# 03_MCU.net
KiCad netlist of a schematic drawn in Altium Designer
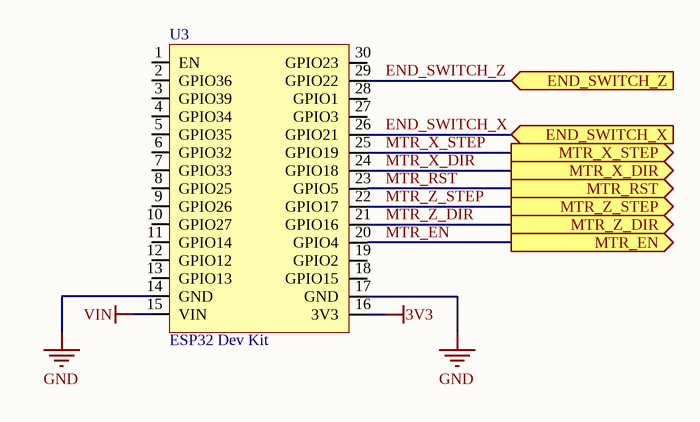
[diagram p0: 03_MCU.SchDoc]

(export (version "E")
  (design (tool "Eeschema 10.0.6"))
  (components
    (comp (ref "U3")
      (value "ESP32 Dev Kit")
      (footprint "Footprint_Misc:ESP32-DevModule")
      (fields
        (field (name "DISTRIBUTOR PART NUMBER") "https://www.aliexpress.com/item/1005001757645011.html")
        (field (name "MANUFACTURER") "Espressif")
      )
      (libsource (lib "Schematic_Misc") (part "ESP32_DEV"))
    )
  )
  (nets
    (net (code "1") (name "/END_SWITCH_X") (class "Default")
      (node (ref "U3") (pin "26") (pinfunction "GPIO21_26") (pintype "passive"))
    )
    (net (code "2") (name "/END_SWITCH_Z") (class "Default")
      (node (ref "U3") (pin "29") (pinfunction "GPIO22_29") (pintype "passive"))
    )
    (net (code "3") (name "/MTR_EN") (class "Default")
      (node (ref "U3") (pin "20") (pinfunction "GPIO4_20") (pintype "passive"))
    )
    (net (code "4") (name "/MTR_RST") (class "Default")
      (node (ref "U3") (pin "23") (pinfunction "GPIO5_23") (pintype "passive"))
    )
    (net (code "5") (name "/MTR_X_DIR") (class "Default")
      (node (ref "U3") (pin "24") (pinfunction "GPIO18_24") (pintype "passive"))
    )
    (net (code "6") (name "/MTR_X_STEP") (class "Default")
      (node (ref "U3") (pin "25") (pinfunction "GPIO19_25") (pintype "passive"))
    )
    (net (code "7") (name "/MTR_Z_DIR") (class "Default")
      (node (ref "U3") (pin "21") (pinfunction "GPIO16_21") (pintype "passive"))
    )
    (net (code "8") (name "/MTR_Z_STEP") (class "Default")
      (node (ref "U3") (pin "22") (pinfunction "GPIO17_22") (pintype "passive"))
    )
    (net (code "9") (name "3V3") (class "Default")
      (node (ref "U3") (pin "16") (pinfunction "3V3_16") (pintype "passive"))
    )
    (net (code "10") (name "GND") (class "Default")
      (node (ref "U3") (pin "14") (pinfunction "GND_14") (pintype "passive"))
      (node (ref "U3") (pin "17") (pinfunction "GND_17") (pintype "passive"))
    )
    (net (code "11") (name "VIN") (class "Default")
      (node (ref "U3") (pin "15") (pinfunction "VIN_15") (pintype "passive"))
    )
    (net (code "12") (name "unconnected-(U3-EN-Pad1)") (class "Default")
      (node (ref "U3") (pin "1") (pinfunction "EN_1") (pintype "passive"))
    )
    (net (code "13") (name "unconnected-(U3-GPIO1-Pad28)") (class "Default")
      (node (ref "U3") (pin "28") (pinfunction "GPIO1_28") (pintype "passive"))
    )
    (net (code "14") (name "unconnected-(U3-GPIO2-Pad19)") (class "Default")
      (node (ref "U3") (pin "19") (pinfunction "GPIO2_19") (pintype "passive"))
    )
    (net (code "15") (name "unconnected-(U3-GPIO3-Pad27)") (class "Default")
      (node (ref "U3") (pin "27") (pinfunction "GPIO3_27") (pintype "passive"))
    )
    (net (code "16") (name "unconnected-(U3-GPIO12-Pad12)") (class "Default")
      (node (ref "U3") (pin "12") (pinfunction "GPIO12_12") (pintype "passive"))
    )
    (net (code "17") (name "unconnected-(U3-GPIO13-Pad13)") (class "Default")
      (node (ref "U3") (pin "13") (pinfunction "GPIO13_13") (pintype "passive"))
    )
    (net (code "18") (name "unconnected-(U3-GPIO14-Pad11)") (class "Default")
      (node (ref "U3") (pin "11") (pinfunction "GPIO14_11") (pintype "passive"))
    )
    (net (code "19") (name "unconnected-(U3-GPIO15-Pad18)") (class "Default")
      (node (ref "U3") (pin "18") (pinfunction "GPIO15_18") (pintype "passive"))
    )
    (net (code "20") (name "unconnected-(U3-GPIO23-Pad30)") (class "Default")
      (node (ref "U3") (pin "30") (pinfunction "GPIO23_30") (pintype "passive"))
    )
    (net (code "21") (name "unconnected-(U3-GPIO25-Pad8)") (class "Default")
      (node (ref "U3") (pin "8") (pinfunction "GPIO25_8") (pintype "passive"))
    )
    (net (code "22") (name "unconnected-(U3-GPIO26-Pad9)") (class "Default")
      (node (ref "U3") (pin "9") (pinfunction "GPIO26_9") (pintype "passive"))
    )
    (net (code "23") (name "unconnected-(U3-GPIO27-Pad10)") (class "Default")
      (node (ref "U3") (pin "10") (pinfunction "GPIO27_10") (pintype "passive"))
    )
    (net (code "24") (name "unconnected-(U3-GPIO32-Pad6)") (class "Default")
      (node (ref "U3") (pin "6") (pinfunction "GPIO32_6") (pintype "passive"))
    )
    (net (code "25") (name "unconnected-(U3-GPIO33-Pad7)") (class "Default")
      (node (ref "U3") (pin "7") (pinfunction "GPIO33_7") (pintype "passive"))
    )
    (net (code "26") (name "unconnected-(U3-GPIO34-Pad4)") (class "Default")
      (node (ref "U3") (pin "4") (pinfunction "GPIO34_4") (pintype "passive"))
    )
    (net (code "27") (name "unconnected-(U3-GPIO35-Pad5)") (class "Default")
      (node (ref "U3") (pin "5") (pinfunction "GPIO35_5") (pintype "passive"))
    )
    (net (code "28") (name "unconnected-(U3-GPIO36-Pad2)") (class "Default")
      (node (ref "U3") (pin "2") (pinfunction "GPIO36_2") (pintype "passive"))
    )
    (net (code "29") (name "unconnected-(U3-GPIO39-Pad3)") (class "Default")
      (node (ref "U3") (pin "3") (pinfunction "GPIO39_3") (pintype "passive"))
    )
  )
)
